# CY8CKIT-032_Schematic.net
KiCad netlist of a schematic drawn in EAGLE
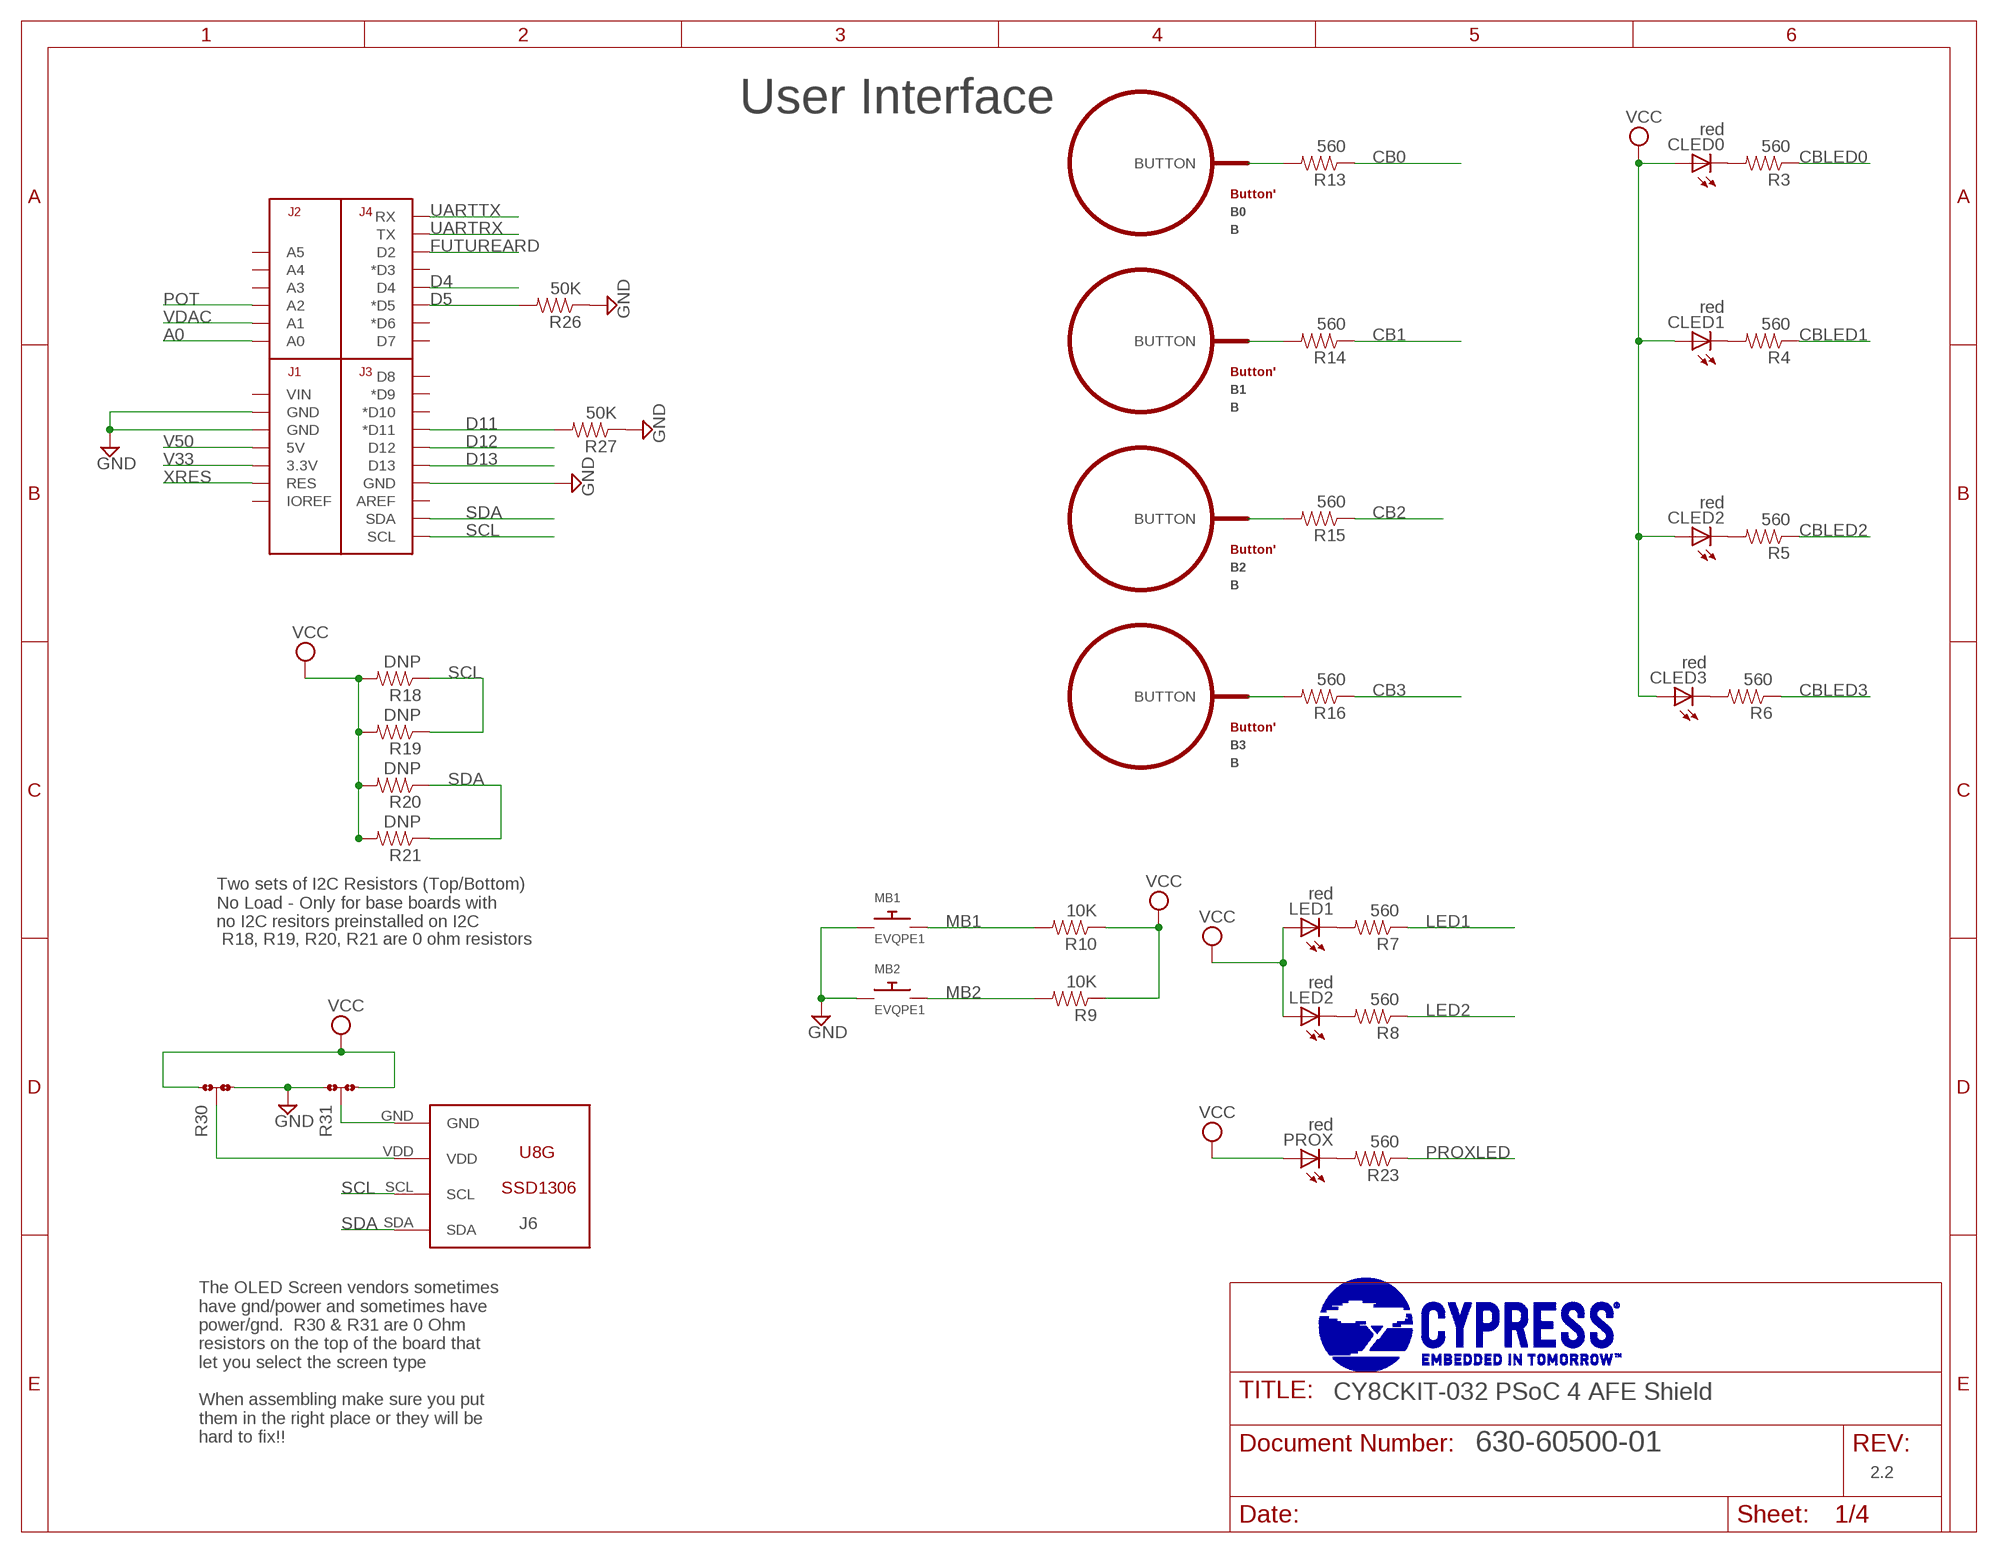
[diagram p0: schematic, sheet 1]
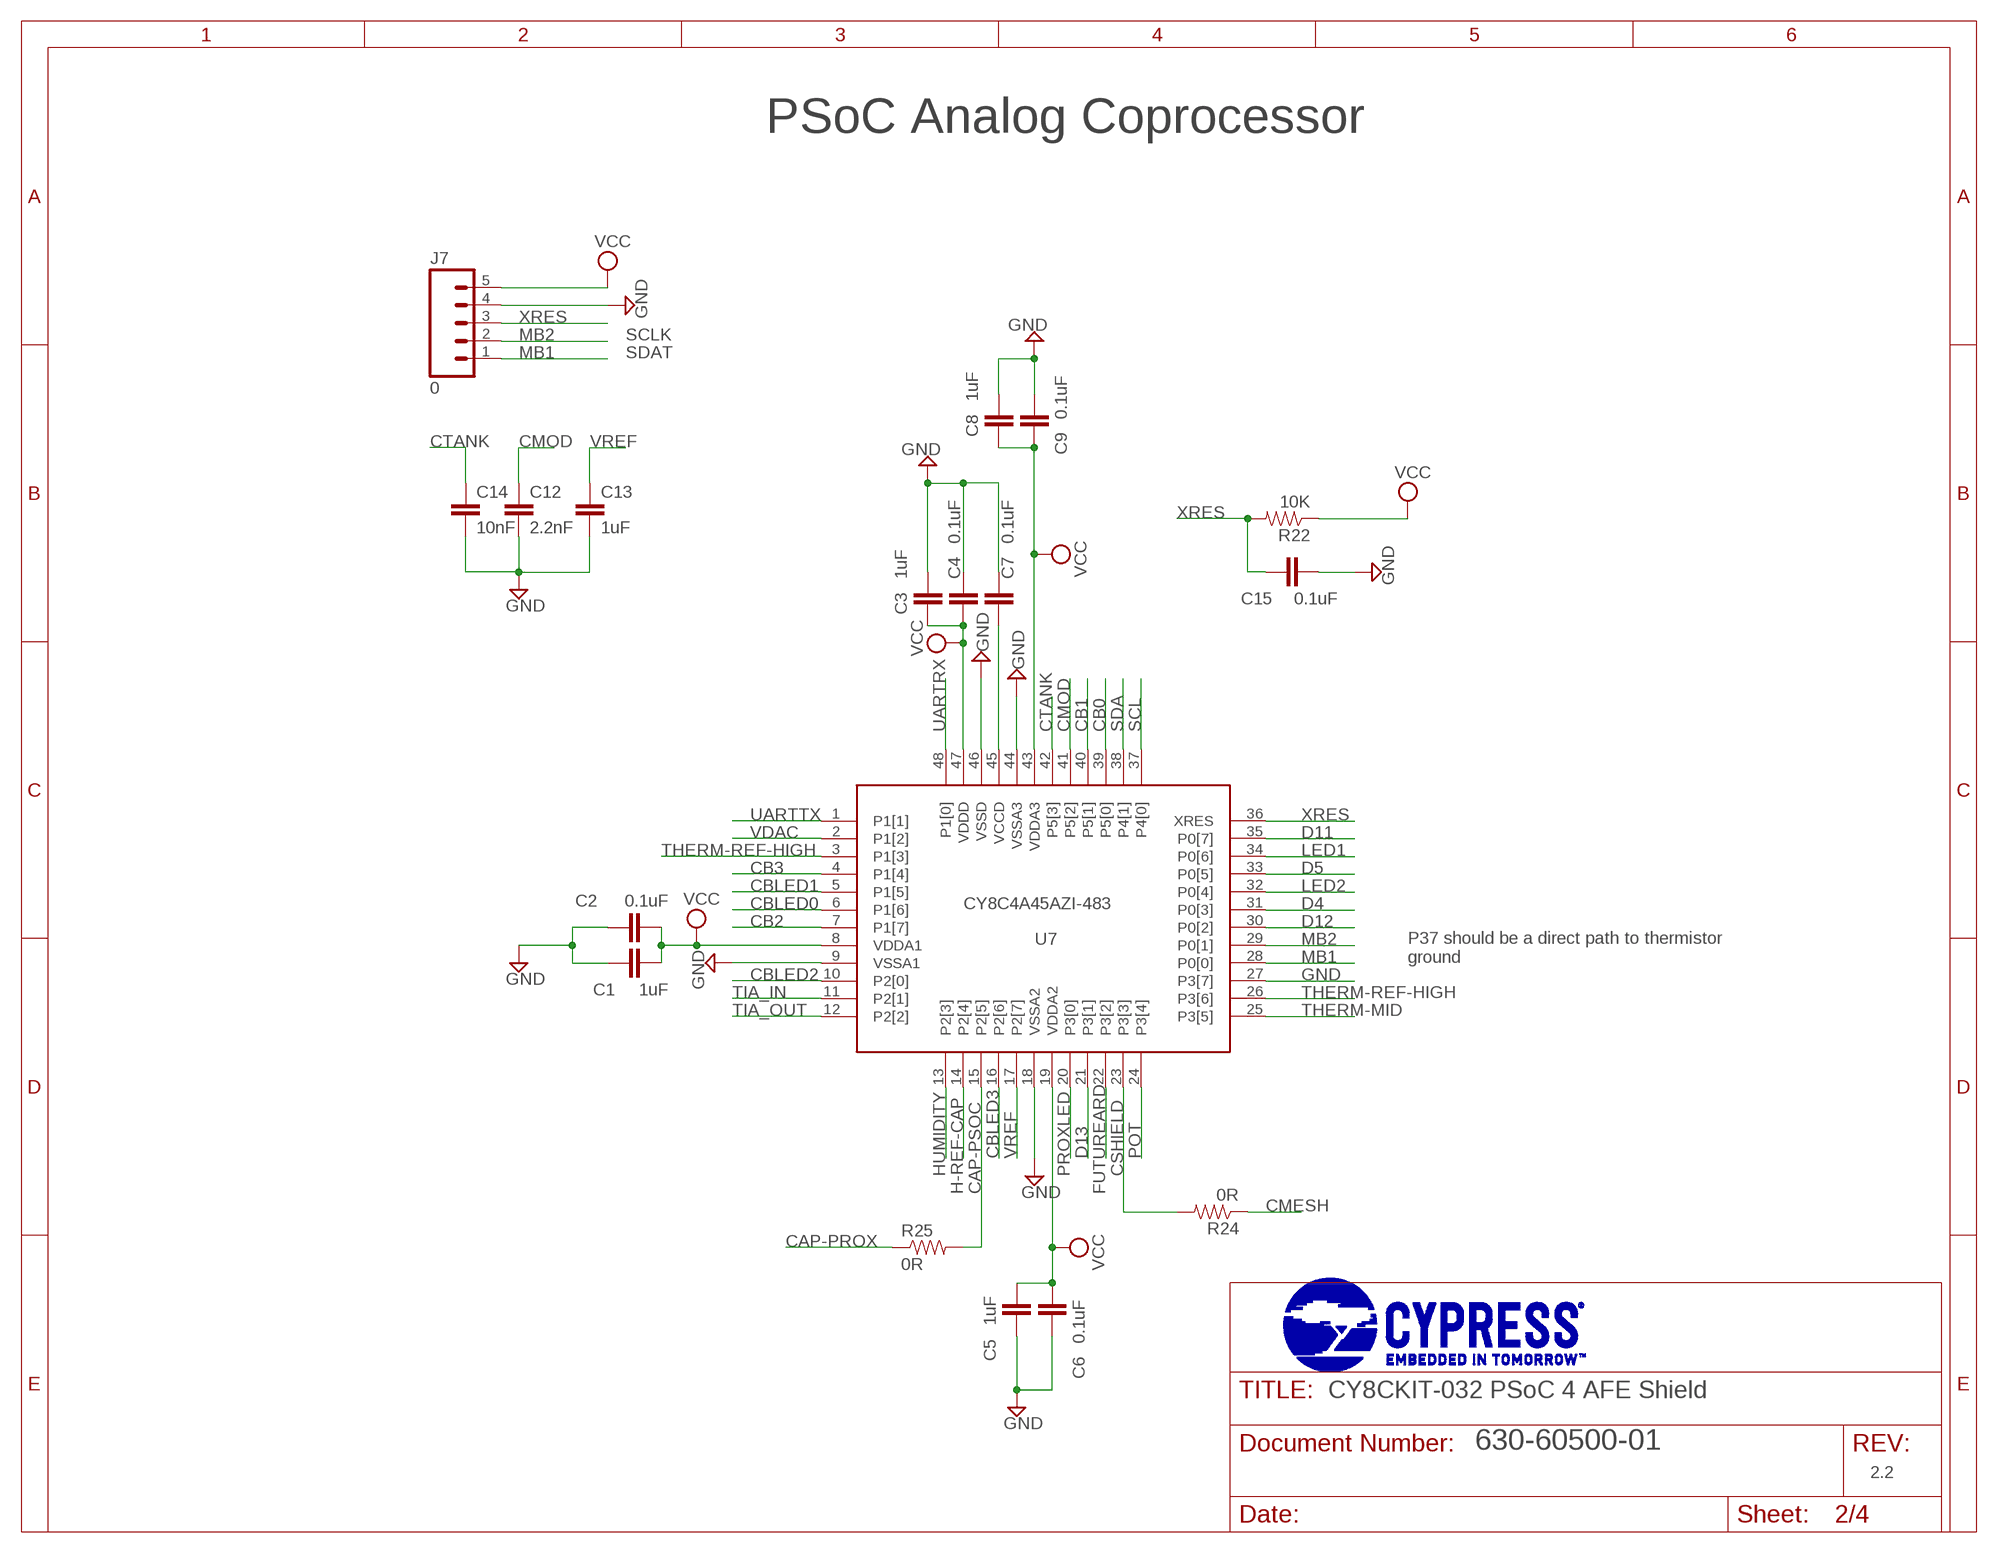
[diagram p1: schematic, sheet 2]
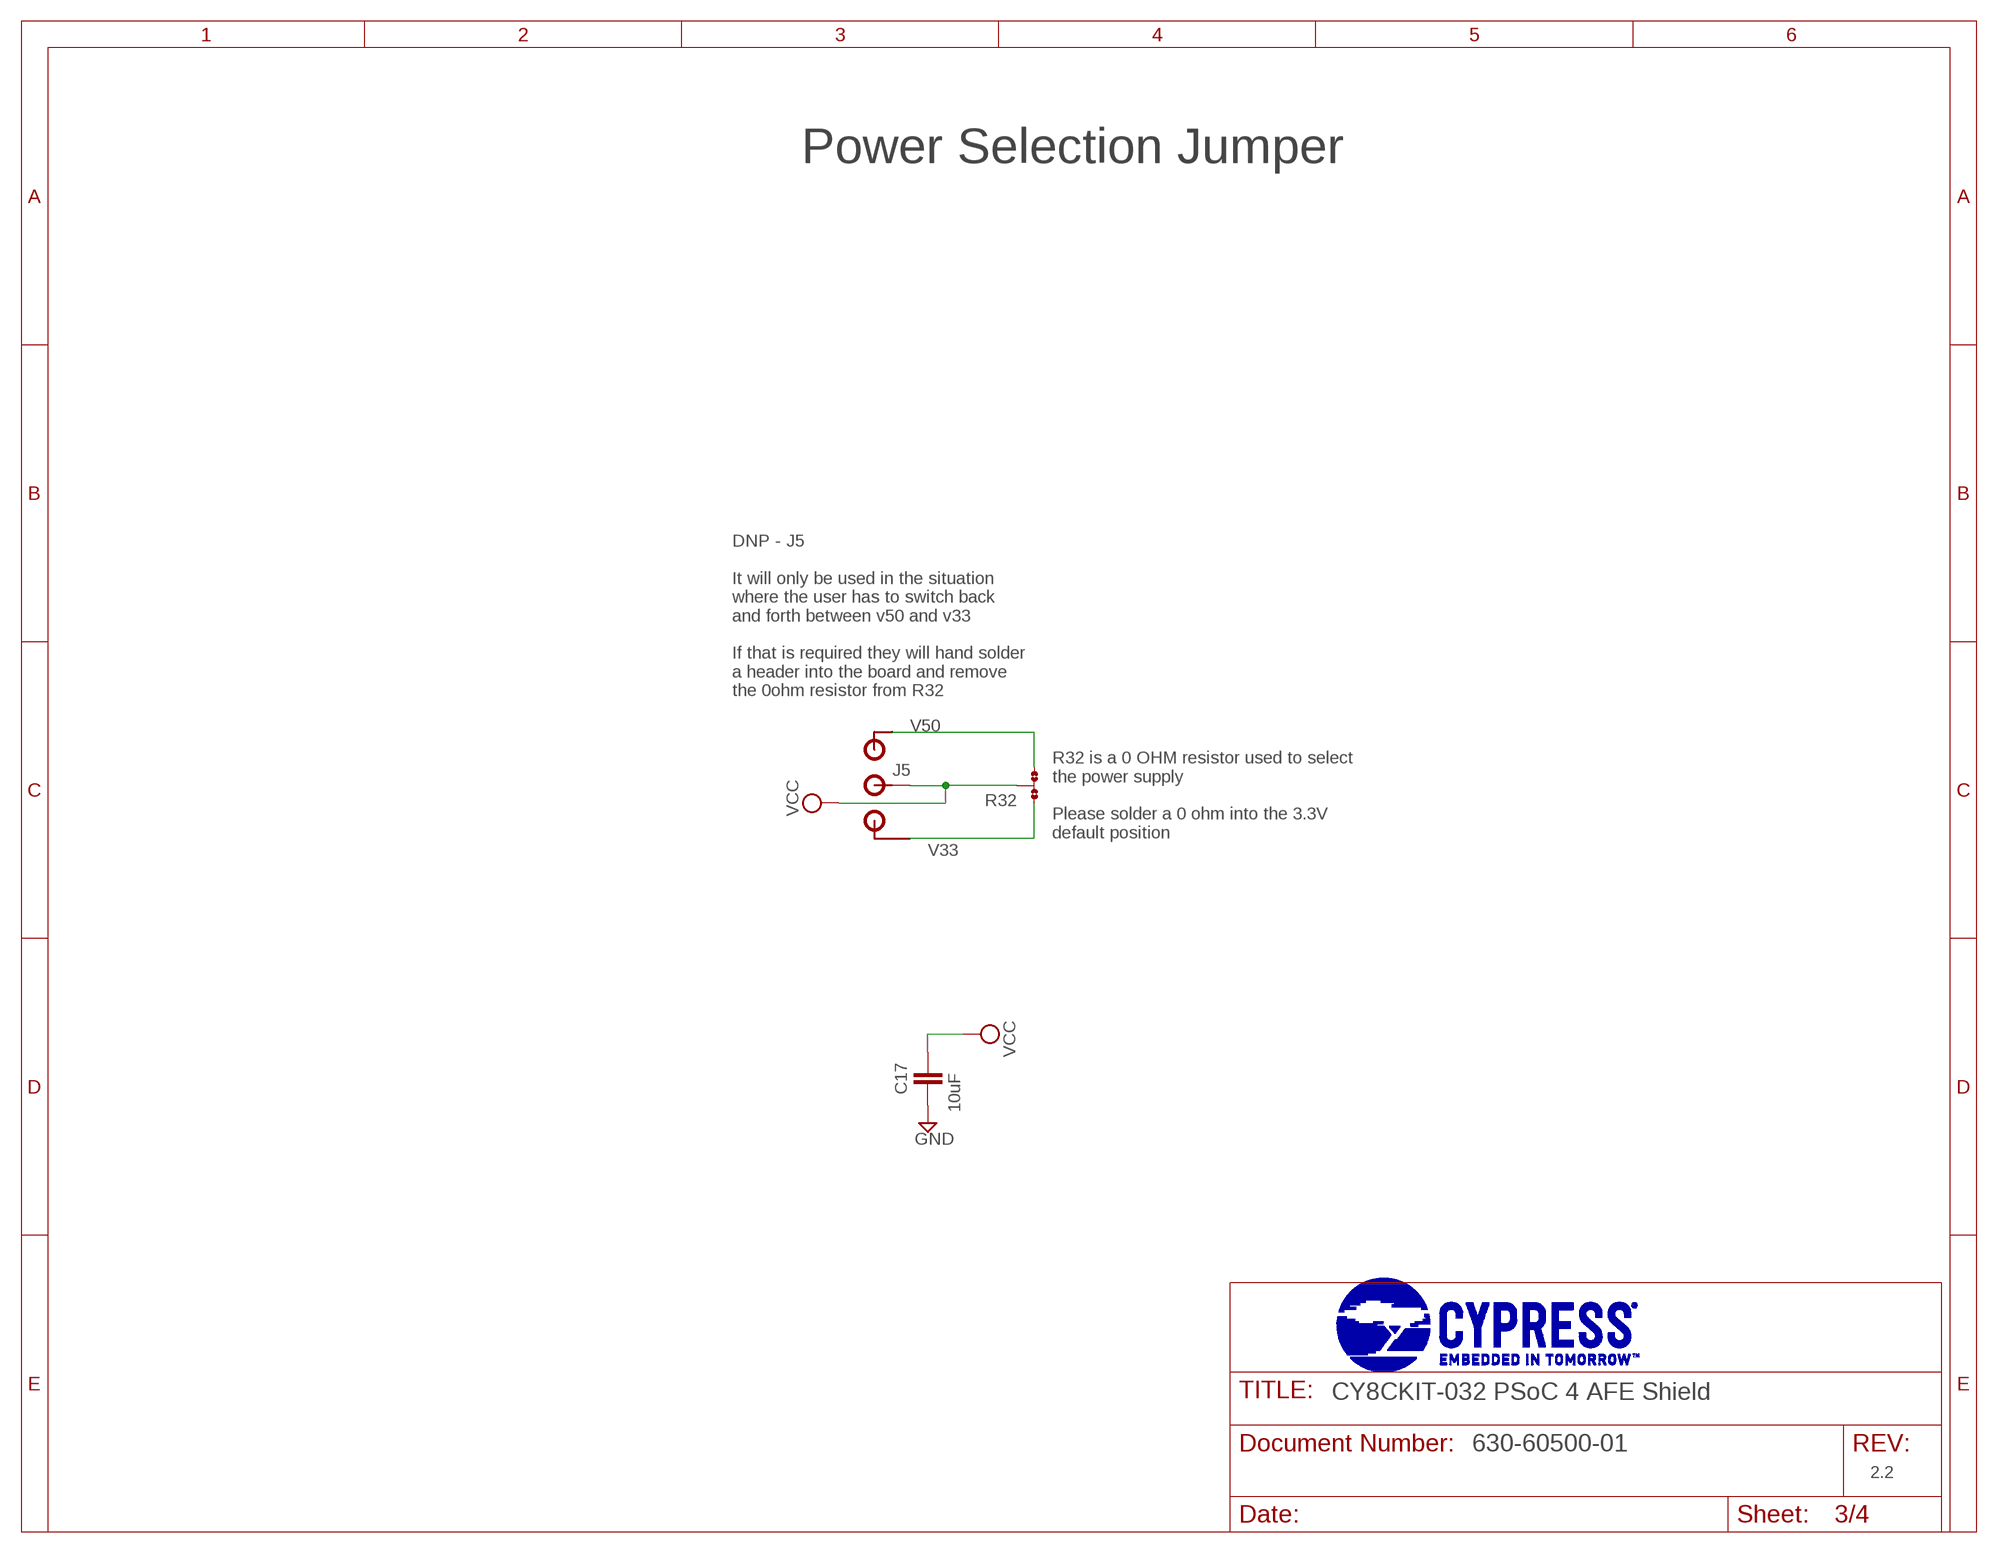
[diagram p2: schematic, sheet 3]
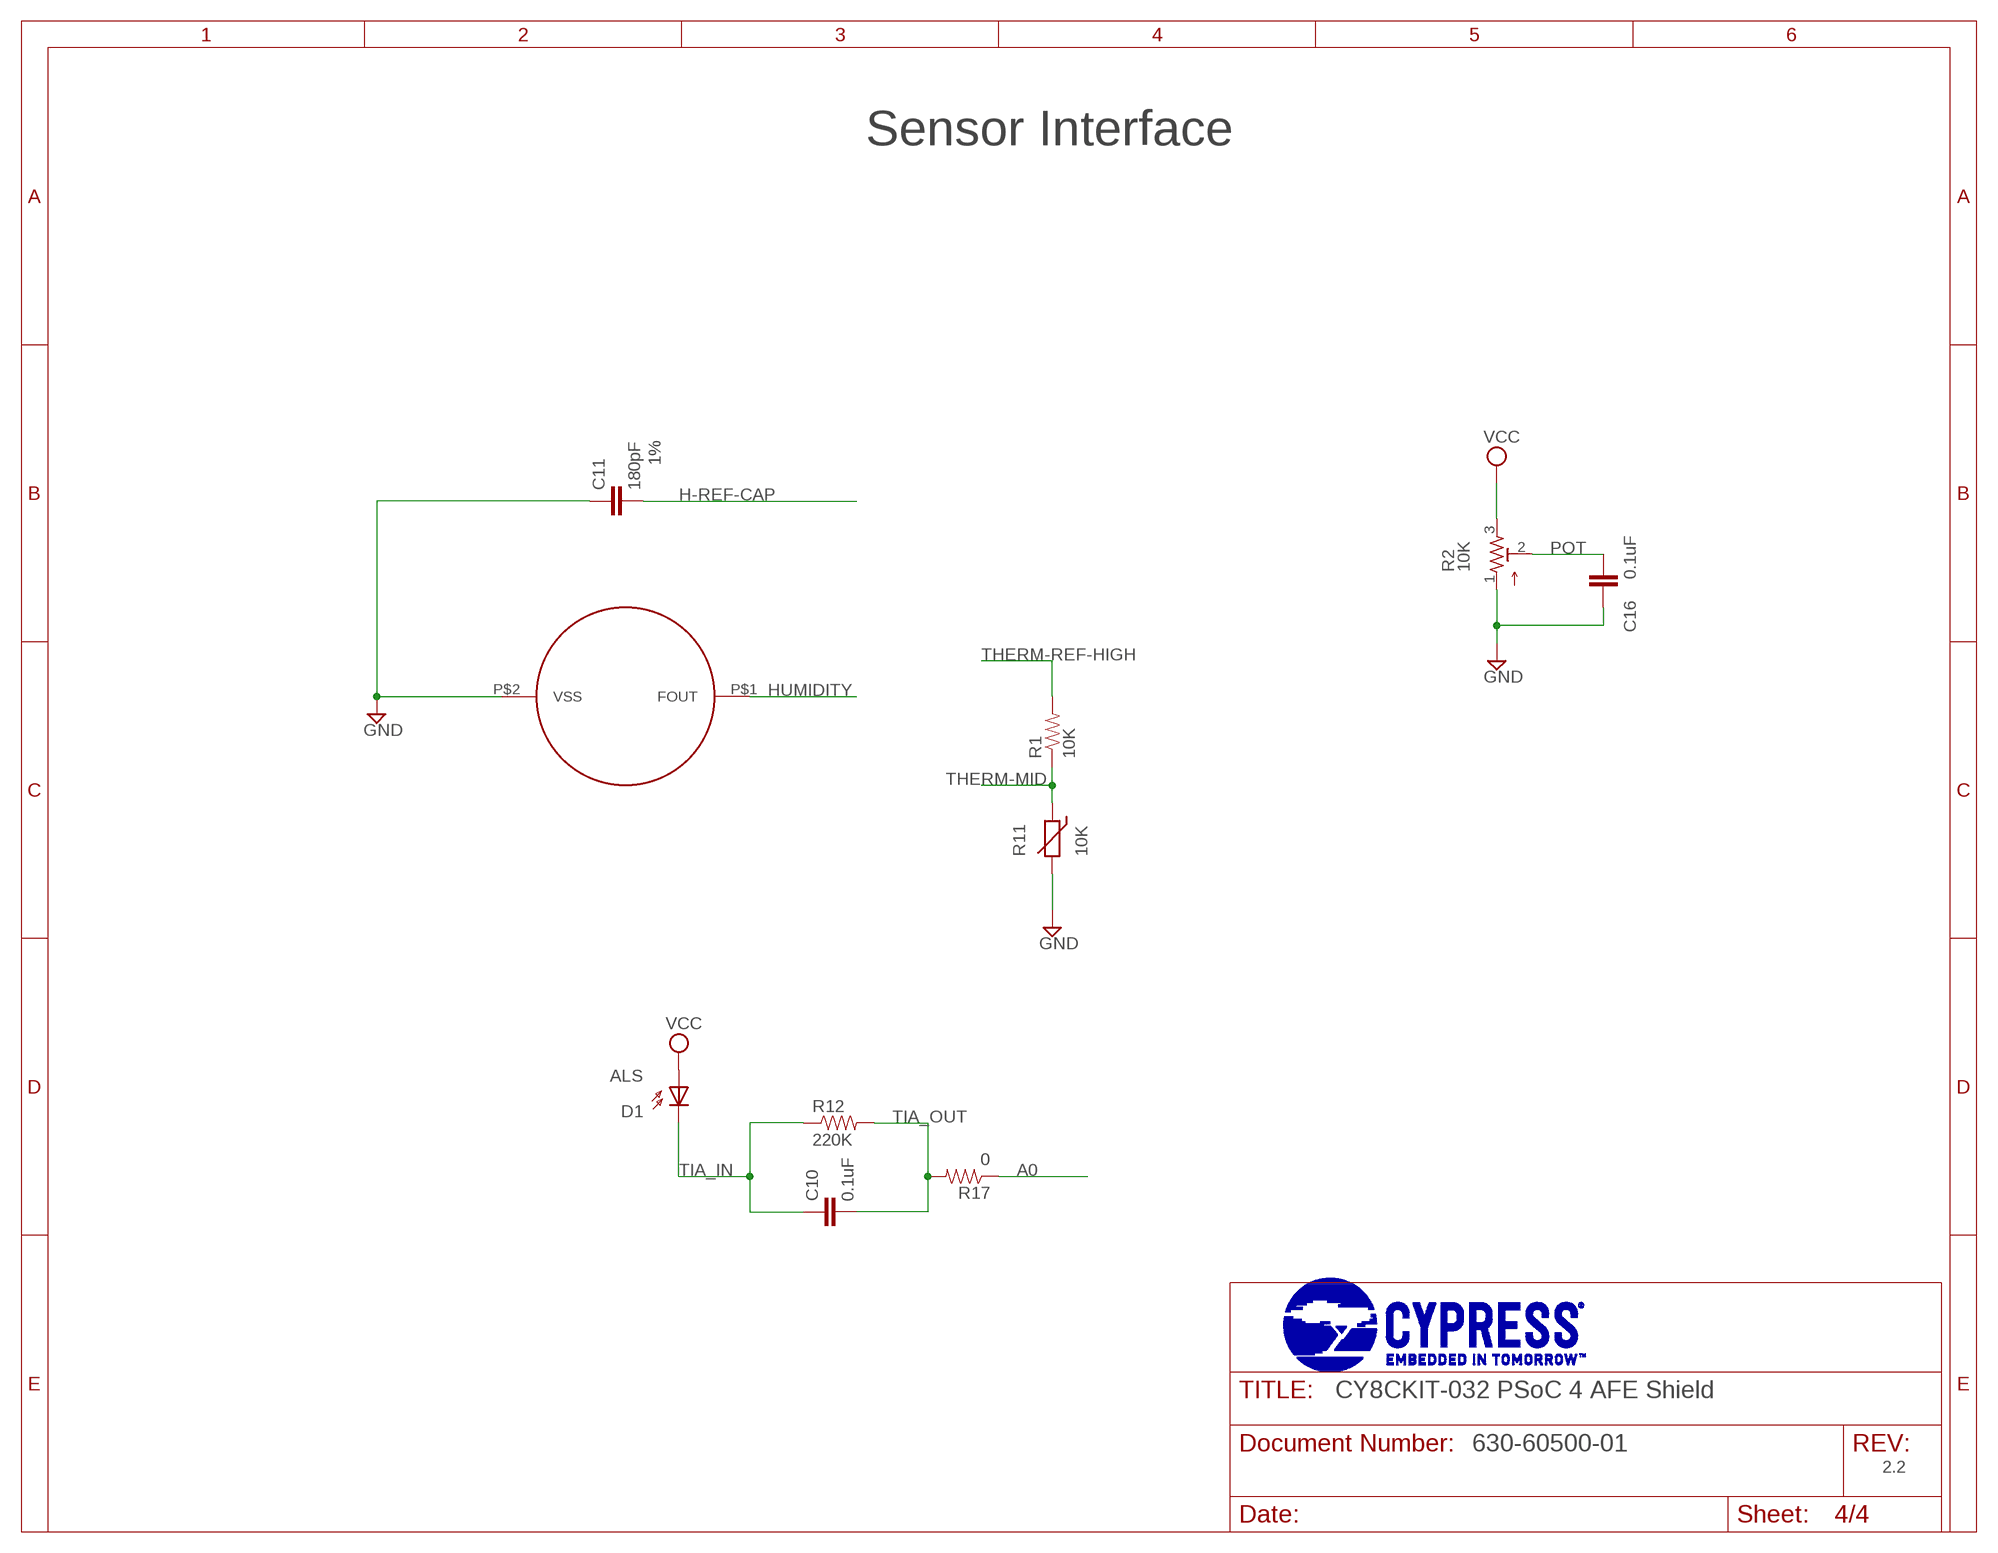
[diagram p3: schematic, sheet 4]

(export (version "E")
  (design (tool "Eeschema 10.0.6"))
  (components
    (comp (ref "C10")
      (value "0.1uF")
      (footprint "eagle-import:0603-CAP")
      (libsource (lib "eagle-import") (part "CAP0603-CAP"))
    )
    (comp (ref "C11")
      (value "180pF")
      (footprint "eagle-import:0603-CAP")
      (libsource (lib "eagle-import") (part "CAP0603-CAP"))
    )
    (comp (ref "C16")
      (value "0.1uF")
      (footprint "eagle-import:0603-CAP")
      (libsource (lib "eagle-import") (part "CAP0603-CAP"))
    )
    (comp (ref "D1")
      (value "ALS")
      (footprint "eagle-import:ALS")
      (libsource (lib "eagle-import") (part "ALS"))
    )
    (comp (ref "HUMIDITY")
      (value "HPP801A031")
      (footprint "eagle-import:HUMIDITY")
      (libsource (lib "eagle-import") (part "HPP801A031"))
    )
    (comp (ref "R1")
      (value "10K")
      (footprint "eagle-import:0603-RES")
      (libsource (lib "eagle-import") (part "RESISTOR0603"))
    )
    (comp (ref "R2")
      (value "10K")
      (footprint "eagle-import:3386P")
      (libsource (lib "eagle-import") (part "TRIM_US-3386P"))
    )
    (comp (ref "R11")
      (value "THERMISTOR-5")
      (footprint "eagle-import:R-5")
      (libsource (lib "eagle-import") (part "THERMISTOR-5"))
    )
    (comp (ref "R12")
      (value "220K")
      (footprint "eagle-import:0603-RES")
      (libsource (lib "eagle-import") (part "RESISTOR0603"))
    )
    (comp (ref "R17")
      (value "0")
      (footprint "eagle-import:0603-RES")
      (libsource (lib "eagle-import") (part "RESISTOR0603"))
    )
    (comp (ref "B0")
      (value "B")
      (footprint "eagle-import:BUTTON_PASSIVE_10MM")
      (libsource (lib "eagle-import") (part "BUTTON_PASSIVE10MM"))
    )
    (comp (ref "B1")
      (value "B")
      (footprint "eagle-import:BUTTON_PASSIVE_10MM")
      (libsource (lib "eagle-import") (part "BUTTON_PASSIVE10MM"))
    )
    (comp (ref "B2")
      (value "B")
      (footprint "eagle-import:BUTTON_PASSIVE_10MM")
      (libsource (lib "eagle-import") (part "BUTTON_PASSIVE10MM"))
    )
    (comp (ref "B3")
      (value "B")
      (footprint "eagle-import:BUTTON_PASSIVE_10MM")
      (libsource (lib "eagle-import") (part "BUTTON_PASSIVE10MM"))
    )
    (comp (ref "CLED0")
      (value "red")
      (footprint "eagle-import:CHIP-LED0603")
      (libsource (lib "eagle-import") (part "LEDCHIP-LED0603"))
    )
    (comp (ref "CLED1")
      (value "red")
      (footprint "eagle-import:CHIP-LED0603")
      (libsource (lib "eagle-import") (part "LEDCHIP-LED0603"))
    )
    (comp (ref "CLED2")
      (value "red")
      (footprint "eagle-import:CHIP-LED0603")
      (libsource (lib "eagle-import") (part "LEDCHIP-LED0603"))
    )
    (comp (ref "CLED3")
      (value "red")
      (footprint "eagle-import:CHIP-LED0603")
      (libsource (lib "eagle-import") (part "LEDCHIP-LED0603"))
    )
    (comp (ref "J6")
      (value "U8G-096-OLED")
      (footprint "eagle-import:096-SSD1306")
      (libsource (lib "eagle-import") (part "U8G-096-OLED"))
    )
    (comp (ref "LED1")
      (value "red")
      (footprint "eagle-import:CHIP-LED0603")
      (libsource (lib "eagle-import") (part "LEDCHIP-LED0603"))
    )
    (comp (ref "LED2")
      (value "red")
      (footprint "eagle-import:CHIP-LED0603")
      (libsource (lib "eagle-import") (part "LEDCHIP-LED0603"))
    )
    (comp (ref "MB1")
      (value "EVQPE1")
      (footprint "eagle-import:SWITCH")
      (libsource (lib "eagle-import") (part "EVQPE1"))
    )
    (comp (ref "MB2")
      (value "EVQPE1")
      (footprint "eagle-import:SWITCH")
      (libsource (lib "eagle-import") (part "EVQPE1"))
    )
    (comp (ref "PROX")
      (value "red")
      (footprint "eagle-import:CHIP-LED0603")
      (libsource (lib "eagle-import") (part "LEDCHIP-LED0603"))
    )
    (comp (ref "R3")
      (value "560")
      (footprint "eagle-import:0603-RES")
      (libsource (lib "eagle-import") (part "RESISTOR0603"))
    )
    (comp (ref "R4")
      (value "560")
      (footprint "eagle-import:0603-RES")
      (libsource (lib "eagle-import") (part "RESISTOR0603"))
    )
    (comp (ref "R5")
      (value "560")
      (footprint "eagle-import:0603-RES")
      (libsource (lib "eagle-import") (part "RESISTOR0603"))
    )
    (comp (ref "R6")
      (value "560")
      (footprint "eagle-import:0603-RES")
      (libsource (lib "eagle-import") (part "RESISTOR0603"))
    )
    (comp (ref "R7")
      (value "560")
      (footprint "eagle-import:0603-RES")
      (libsource (lib "eagle-import") (part "RESISTOR0603"))
    )
    (comp (ref "R8")
      (value "560")
      (footprint "eagle-import:0603-RES")
      (libsource (lib "eagle-import") (part "RESISTOR0603"))
    )
    (comp (ref "R9")
      (value "10K")
      (footprint "eagle-import:0603-RES")
      (libsource (lib "eagle-import") (part "RESISTOR0603"))
    )
    (comp (ref "R10")
      (value "10K")
      (footprint "eagle-import:0603-RES")
      (libsource (lib "eagle-import") (part "RESISTOR0603"))
    )
    (comp (ref "R13")
      (value "560")
      (footprint "eagle-import:0603-RES")
      (libsource (lib "eagle-import") (part "RESISTOR0603"))
    )
    (comp (ref "R14")
      (value "560")
      (footprint "eagle-import:0603-RES")
      (libsource (lib "eagle-import") (part "RESISTOR0603"))
    )
    (comp (ref "R15")
      (value "560")
      (footprint "eagle-import:0603-RES")
      (libsource (lib "eagle-import") (part "RESISTOR0603"))
    )
    (comp (ref "R16")
      (value "560")
      (footprint "eagle-import:0603-RES")
      (libsource (lib "eagle-import") (part "RESISTOR0603"))
    )
    (comp (ref "R18")
      (value "DNP")
      (footprint "eagle-import:0603-RES")
      (libsource (lib "eagle-import") (part "RESISTOR0603"))
    )
    (comp (ref "R19")
      (value "DNP")
      (footprint "eagle-import:0603-RES")
      (libsource (lib "eagle-import") (part "RESISTOR0603"))
    )
    (comp (ref "R20")
      (value "DNP")
      (footprint "eagle-import:0603-RES")
      (libsource (lib "eagle-import") (part "RESISTOR0603"))
    )
    (comp (ref "R21")
      (value "DNP")
      (footprint "eagle-import:0603-RES")
      (libsource (lib "eagle-import") (part "RESISTOR0603"))
    )
    (comp (ref "R23")
      (value "560")
      (footprint "eagle-import:0603-RES")
      (libsource (lib "eagle-import") (part "RESISTOR0603"))
    )
    (comp (ref "R26")
      (value "50K")
      (footprint "eagle-import:0603-RES")
      (libsource (lib "eagle-import") (part "RESISTOR0603"))
    )
    (comp (ref "R27")
      (value "50K")
      (footprint "eagle-import:0603-RES")
      (libsource (lib "eagle-import") (part "RESISTOR0603"))
    )
    (comp (ref "R30")
      (value "JMP-3-1_2")
      (footprint "eagle-import:JMP-3-1_2")
      (libsource (lib "eagle-import") (part "JMP-3-1_2"))
    )
    (comp (ref "R31")
      (value "JMP-3-2_3")
      (footprint "eagle-import:JMP-3-2_3")
      (libsource (lib "eagle-import") (part "JMP-3-2_3"))
    )
    (comp (ref "U$1")
      (value "ARDUINO_R3_SHIELDNOLABELS")
      (footprint "eagle-import:UNO_R3_SHIELD_NOLABELS")
      (libsource (lib "eagle-import") (part "ARDUINO_R3_SHIELDNOLABELS"))
    )
    (comp (ref "C1")
      (value "1uF")
      (footprint "eagle-import:0603-CAP")
      (libsource (lib "eagle-import") (part "CAP0603-CAP"))
    )
    (comp (ref "C2")
      (value "0.1uF")
      (footprint "eagle-import:0603-CAP")
      (libsource (lib "eagle-import") (part "CAP0603-CAP"))
    )
    (comp (ref "C3")
      (value "1uF")
      (footprint "eagle-import:0603-CAP")
      (libsource (lib "eagle-import") (part "CAP0603-CAP"))
    )
    (comp (ref "C4")
      (value "0.1uF")
      (footprint "eagle-import:0603-CAP")
      (libsource (lib "eagle-import") (part "CAP0603-CAP"))
    )
    (comp (ref "C5")
      (value "1uF")
      (footprint "eagle-import:0603-CAP")
      (libsource (lib "eagle-import") (part "CAP0603-CAP"))
    )
    (comp (ref "C6")
      (value "0.1uF")
      (footprint "eagle-import:0603-CAP")
      (libsource (lib "eagle-import") (part "CAP0603-CAP"))
    )
    (comp (ref "C7")
      (value "0.1uF")
      (footprint "eagle-import:0603-CAP")
      (libsource (lib "eagle-import") (part "CAP0603-CAP"))
    )
    (comp (ref "C8")
      (value "1uF")
      (footprint "eagle-import:0603-CAP")
      (libsource (lib "eagle-import") (part "CAP0603-CAP"))
    )
    (comp (ref "C9")
      (value "0.1uF")
      (footprint "eagle-import:0603-CAP")
      (libsource (lib "eagle-import") (part "CAP0603-CAP"))
    )
    (comp (ref "C12")
      (value "2.2nF")
      (footprint "eagle-import:0603-CAP")
      (libsource (lib "eagle-import") (part "CAP0603-CAP"))
    )
    (comp (ref "C13")
      (value "1uF")
      (footprint "eagle-import:0603-CAP")
      (libsource (lib "eagle-import") (part "CAP0603-CAP"))
    )
    (comp (ref "C14")
      (value "10nF")
      (footprint "eagle-import:0603-CAP")
      (libsource (lib "eagle-import") (part "CAP0603-CAP"))
    )
    (comp (ref "C15")
      (value "0.1uF")
      (footprint "eagle-import:0603-CAP")
      (libsource (lib "eagle-import") (part "CAP0603-CAP"))
    )
    (comp (ref "J7")
      (value "0")
      (footprint "eagle-import:1X05_LOCK")
      (libsource (lib "eagle-import") (part "M05LOCK"))
    )
    (comp (ref "R22")
      (value "10K")
      (footprint "eagle-import:0603-RES")
      (libsource (lib "eagle-import") (part "RESISTOR0603"))
    )
    (comp (ref "R24")
      (value "0R")
      (footprint "eagle-import:0603-RES")
      (libsource (lib "eagle-import") (part "RESISTOR0603"))
    )
    (comp (ref "R25")
      (value "0R")
      (footprint "eagle-import:0603-RES")
      (libsource (lib "eagle-import") (part "RESISTOR0603"))
    )
    (comp (ref "U7")
      (value "CY8C4A45-48")
      (footprint "eagle-import:TQFP-7X7-48")
      (libsource (lib "eagle-import") (part "CY8C4A45-48"))
    )
    (comp (ref "C17")
      (value "10uF")
      (footprint "eagle-import:0603-CAP")
      (libsource (lib "eagle-import") (part "CAP0603-CAP"))
    )
    (comp (ref "J5")
      (value "vcc")
      (footprint "eagle-import:JMP-3-NO-PTH-2.54")
      (libsource (lib "eagle-import") (part "JMP-3-PTH-PTH"))
    )
    (comp (ref "R32")
      (value "3.3v")
      (footprint "eagle-import:JMP-3-NO")
      (libsource (lib "eagle-import") (part "JMP-3-NO"))
    )
  )
  (nets
    (net (code "1") (name "A0") (class "Default")
      (node (ref "R17") (pin "1") (pinfunction "1_1") (pintype "passive"))
      (node (ref "U$1") (pin "A0") (pinfunction "A0_A0") (pintype "bidirectional"))
    )
    (net (code "2") (name "CAP-PROX") (class "Default")
      (node (ref "R25") (pin "1") (pinfunction "1_1") (pintype "passive"))
    )
    (net (code "3") (name "CAP-PSOC") (class "Default")
      (node (ref "R25") (pin "2") (pinfunction "2_2") (pintype "passive"))
      (node (ref "U7") (pin "15") (pinfunction "P2[5]_15") (pintype "bidirectional"))
    )
    (net (code "4") (name "CB0") (class "Default")
      (node (ref "R13") (pin "1") (pinfunction "1_1") (pintype "passive"))
      (node (ref "U7") (pin "39") (pinfunction "P5[0]_39") (pintype "bidirectional"))
    )
    (net (code "5") (name "CB1") (class "Default")
      (node (ref "R14") (pin "1") (pinfunction "1_1") (pintype "passive"))
      (node (ref "U7") (pin "40") (pinfunction "P5[1]_40") (pintype "bidirectional"))
    )
    (net (code "6") (name "CB2") (class "Default")
      (node (ref "R15") (pin "1") (pinfunction "1_1") (pintype "passive"))
      (node (ref "U7") (pin "7") (pinfunction "P1[7]_7") (pintype "bidirectional"))
    )
    (net (code "7") (name "CB3") (class "Default")
      (node (ref "R16") (pin "1") (pinfunction "1_1") (pintype "passive"))
      (node (ref "U7") (pin "4") (pinfunction "P1[4]_4") (pintype "bidirectional"))
    )
    (net (code "8") (name "CBLED0") (class "Default")
      (node (ref "R3") (pin "1") (pinfunction "1_1") (pintype "passive"))
      (node (ref "U7") (pin "6") (pinfunction "P1[6]_6") (pintype "bidirectional"))
    )
    (net (code "9") (name "CBLED1") (class "Default")
      (node (ref "R4") (pin "1") (pinfunction "1_1") (pintype "passive"))
      (node (ref "U7") (pin "5") (pinfunction "P1[5]_5") (pintype "bidirectional"))
    )
    (net (code "10") (name "CBLED2") (class "Default")
      (node (ref "R5") (pin "1") (pinfunction "1_1") (pintype "passive"))
      (node (ref "U7") (pin "10") (pinfunction "P2[0]_10") (pintype "bidirectional"))
    )
    (net (code "11") (name "CBLED3") (class "Default")
      (node (ref "R6") (pin "1") (pinfunction "1_1") (pintype "passive"))
      (node (ref "U7") (pin "16") (pinfunction "P2[6]_16") (pintype "bidirectional"))
    )
    (net (code "12") (name "CMESH") (class "Default")
      (node (ref "R24") (pin "1") (pinfunction "1_1") (pintype "passive"))
    )
    (net (code "13") (name "CMOD") (class "Default")
      (node (ref "C12") (pin "1") (pinfunction "1_1") (pintype "passive"))
      (node (ref "U7") (pin "41") (pinfunction "P5[2]_41") (pintype "bidirectional"))
    )
    (net (code "14") (name "CSHIELD") (class "Default")
      (node (ref "R24") (pin "2") (pinfunction "2_2") (pintype "passive"))
      (node (ref "U7") (pin "23") (pinfunction "P3[3]_23") (pintype "bidirectional"))
    )
    (net (code "15") (name "CTANK") (class "Default")
      (node (ref "C14") (pin "1") (pinfunction "1_1") (pintype "passive"))
      (node (ref "U7") (pin "42") (pinfunction "P5[3]_42") (pintype "bidirectional"))
    )
    (net (code "16") (name "D4") (class "Default")
      (node (ref "U$1") (pin "D4") (pinfunction "D4_D4") (pintype "bidirectional"))
      (node (ref "U7") (pin "31") (pinfunction "P0[3]_31") (pintype "bidirectional"))
    )
    (net (code "17") (name "D5") (class "Default")
      (node (ref "R26") (pin "2") (pinfunction "2_2") (pintype "passive"))
      (node (ref "U$1") (pin "D5") (pinfunction "*D5_D5") (pintype "bidirectional"))
      (node (ref "U7") (pin "33") (pinfunction "P0[5]_33") (pintype "bidirectional"))
    )
    (net (code "18") (name "D11") (class "Default")
      (node (ref "R27") (pin "2") (pinfunction "2_2") (pintype "passive"))
      (node (ref "U$1") (pin "D11") (pinfunction "*D11_D11") (pintype "bidirectional"))
      (node (ref "U7") (pin "35") (pinfunction "P0[7]_35") (pintype "bidirectional"))
    )
    (net (code "19") (name "D12") (class "Default")
      (node (ref "U$1") (pin "D12") (pinfunction "D12_D12") (pintype "bidirectional"))
      (node (ref "U7") (pin "30") (pinfunction "P0[2]_30") (pintype "bidirectional"))
    )
    (net (code "20") (name "D13") (class "Default")
      (node (ref "U$1") (pin "D13") (pinfunction "D13_D13") (pintype "bidirectional"))
      (node (ref "U7") (pin "21") (pinfunction "P3[1]_21") (pintype "bidirectional"))
    )
    (net (code "21") (name "FUTUREARD") (class "Default")
      (node (ref "U$1") (pin "D2") (pinfunction "D2_D2") (pintype "bidirectional"))
      (node (ref "U7") (pin "22") (pinfunction "P3[2]_22") (pintype "bidirectional"))
    )
    (net (code "22") (name "GND") (class "Default")
      (node (ref "C1") (pin "1") (pinfunction "1_1") (pintype "passive"))
      (node (ref "C11") (pin "1") (pinfunction "1_1") (pintype "passive"))
      (node (ref "C12") (pin "2") (pinfunction "2_2") (pintype "passive"))
      (node (ref "C13") (pin "2") (pinfunction "2_2") (pintype "passive"))
      (node (ref "C14") (pin "2") (pinfunction "2_2") (pintype "passive"))
      (node (ref "C15") (pin "1") (pinfunction "1_1") (pintype "passive"))
      (node (ref "C16") (pin "2") (pinfunction "2_2") (pintype "passive"))
      (node (ref "C17") (pin "2") (pinfunction "2_2") (pintype "passive"))
      (node (ref "C2") (pin "1") (pinfunction "1_1") (pintype "passive"))
      (node (ref "C3") (pin "1") (pinfunction "1_1") (pintype "passive"))
      (node (ref "C4") (pin "1") (pinfunction "1_1") (pintype "passive"))
      (node (ref "C5") (pin "2") (pinfunction "2_2") (pintype "passive"))
      (node (ref "C6") (pin "2") (pinfunction "2_2") (pintype "passive"))
      (node (ref "C7") (pin "1") (pinfunction "1_1") (pintype "passive"))
      (node (ref "C8") (pin "1") (pinfunction "1_1") (pintype "passive"))
      (node (ref "C9") (pin "1") (pinfunction "1_1") (pintype "passive"))
      (node (ref "HUMIDITY") (pin "P$2") (pinfunction "VSS_P$2") (pintype "bidirectional"))
      (node (ref "J7") (pin "4") (pinfunction "4_4") (pintype "passive"))
      (node (ref "MB1") (pin "P$1") (pinfunction "P$1_P$1") (pintype "passive"))
      (node (ref "MB2") (pin "P$1") (pinfunction "P$1_P$1") (pintype "passive"))
      (node (ref "R11") (pin "2") (pinfunction "2_2") (pintype "passive"))
      (node (ref "R2") (pin "1") (pinfunction "1_1") (pintype "passive"))
      (node (ref "R26") (pin "1") (pinfunction "1_1") (pintype "passive"))
      (node (ref "R27") (pin "1") (pinfunction "1_1") (pintype "passive"))
      (node (ref "R30") (pin "3") (pinfunction "3_3") (pintype "passive"))
      (node (ref "R31") (pin "1") (pinfunction "1_1") (pintype "passive"))
      (node (ref "U$1") (pin "GND@0") (pinfunction "GND_GND@0") (pintype "bidirectional"))
      (node (ref "U$1") (pin "GND@1") (pinfunction "GND_GND@1") (pintype "bidirectional"))
      (node (ref "U$1") (pin "GND@2") (pinfunction "GND_GND@2") (pintype "bidirectional"))
      (node (ref "U7") (pin "18") (pinfunction "VSSA2_18") (pintype "bidirectional"))
      (node (ref "U7") (pin "27") (pinfunction "P3[7]_27") (pintype "bidirectional"))
      (node (ref "U7") (pin "44") (pinfunction "VSSA3_44") (pintype "bidirectional"))
      (node (ref "U7") (pin "46") (pinfunction "VSSD_46") (pintype "bidirectional"))
      (node (ref "U7") (pin "9") (pinfunction "VSSA1_9") (pintype "bidirectional"))
    )
    (net (code "23") (name "H-REF-CAP") (class "Default")
      (node (ref "C11") (pin "2") (pinfunction "2_2") (pintype "passive"))
      (node (ref "U7") (pin "14") (pinfunction "P2[4]_14") (pintype "bidirectional"))
    )
    (net (code "24") (name "HUMIDITY") (class "Default")
      (node (ref "HUMIDITY") (pin "P$1") (pinfunction "FOUT_P$1") (pintype "bidirectional"))
      (node (ref "U7") (pin "13") (pinfunction "P2[3]_13") (pintype "bidirectional"))
    )
    (net (code "25") (name "LED1") (class "Default")
      (node (ref "R7") (pin "1") (pinfunction "1_1") (pintype "passive"))
      (node (ref "U7") (pin "34") (pinfunction "P0[6]_34") (pintype "bidirectional"))
    )
    (net (code "26") (name "LED2") (class "Default")
      (node (ref "R8") (pin "1") (pinfunction "1_1") (pintype "passive"))
      (node (ref "U7") (pin "32") (pinfunction "P0[4]_32") (pintype "bidirectional"))
    )
    (net (code "27") (name "MB1") (class "Default")
      (node (ref "J7") (pin "1") (pinfunction "1_1") (pintype "passive"))
      (node (ref "MB1") (pin "P$2") (pinfunction "P$2_P$2") (pintype "passive"))
      (node (ref "R10") (pin "2") (pinfunction "2_2") (pintype "passive"))
      (node (ref "U7") (pin "28") (pinfunction "P0[0]_28") (pintype "bidirectional"))
    )
    (net (code "28") (name "MB2") (class "Default")
      (node (ref "J7") (pin "2") (pinfunction "2_2") (pintype "passive"))
      (node (ref "MB2") (pin "P$2") (pinfunction "P$2_P$2") (pintype "passive"))
      (node (ref "R9") (pin "2") (pinfunction "2_2") (pintype "passive"))
      (node (ref "U7") (pin "29") (pinfunction "P0[1]_29") (pintype "bidirectional"))
    )
    (net (code "29") (name "Net-(B0-PadBUTTON)") (class "Default")
      (node (ref "B0") (pin "BUTTON") (pinfunction "BUTTON_BUTTON") (pintype "passive"))
      (node (ref "R13") (pin "2") (pinfunction "2_2") (pintype "passive"))
    )
    (net (code "30") (name "Net-(B1-PadBUTTON)") (class "Default")
      (node (ref "B1") (pin "BUTTON") (pinfunction "BUTTON_BUTTON") (pintype "passive"))
      (node (ref "R14") (pin "2") (pinfunction "2_2") (pintype "passive"))
    )
    (net (code "31") (name "Net-(B2-PadBUTTON)") (class "Default")
      (node (ref "B2") (pin "BUTTON") (pinfunction "BUTTON_BUTTON") (pintype "passive"))
      (node (ref "R15") (pin "2") (pinfunction "2_2") (pintype "passive"))
    )
    (net (code "32") (name "Net-(B3-PadBUTTON)") (class "Default")
      (node (ref "B3") (pin "BUTTON") (pinfunction "BUTTON_BUTTON") (pintype "passive"))
      (node (ref "R16") (pin "2") (pinfunction "2_2") (pintype "passive"))
    )
    (net (code "33") (name "Net-(CLED0-PadC)") (class "Default")
      (node (ref "CLED0") (pin "C") (pinfunction "C_C") (pintype "passive"))
      (node (ref "R3") (pin "2") (pinfunction "2_2") (pintype "passive"))
    )
    (net (code "34") (name "Net-(CLED1-PadC)") (class "Default")
      (node (ref "CLED1") (pin "C") (pinfunction "C_C") (pintype "passive"))
      (node (ref "R4") (pin "2") (pinfunction "2_2") (pintype "passive"))
    )
    (net (code "35") (name "Net-(CLED2-PadC)") (class "Default")
      (node (ref "CLED2") (pin "C") (pinfunction "C_C") (pintype "passive"))
      (node (ref "R5") (pin "2") (pinfunction "2_2") (pintype "passive"))
    )
    (net (code "36") (name "Net-(CLED3-PadC)") (class "Default")
      (node (ref "CLED3") (pin "C") (pinfunction "C_C") (pintype "passive"))
      (node (ref "R6") (pin "2") (pinfunction "2_2") (pintype "passive"))
    )
    (net (code "37") (name "Net-(J6-PadGND)") (class "Default")
      (node (ref "J6") (pin "GND") (pinfunction "GND_GND") (pintype "power_in"))
      (node (ref "R31") (pin "2") (pinfunction "2_2") (pintype "passive"))
    )
    (net (code "38") (name "Net-(J6-PadVDD)") (class "Default")
      (node (ref "J6") (pin "VDD") (pinfunction "VDD_VDD") (pintype "power_in"))
      (node (ref "R30") (pin "2") (pinfunction "2_2") (pintype "passive"))
    )
    (net (code "39") (name "Net-(LED1-PadC)") (class "Default")
      (node (ref "LED1") (pin "C") (pinfunction "C_C") (pintype "passive"))
      (node (ref "R7") (pin "2") (pinfunction "2_2") (pintype "passive"))
    )
    (net (code "40") (name "Net-(LED2-PadC)") (class "Default")
      (node (ref "LED2") (pin "C") (pinfunction "C_C") (pintype "passive"))
      (node (ref "R8") (pin "2") (pinfunction "2_2") (pintype "passive"))
    )
    (net (code "41") (name "Net-(PROX-PadC)") (class "Default")
      (node (ref "PROX") (pin "C") (pinfunction "C_C") (pintype "passive"))
      (node (ref "R23") (pin "2") (pinfunction "2_2") (pintype "passive"))
    )
    (net (code "42") (name "Net-(U7-VCCD)") (class "Default")
      (node (ref "C7") (pin "2") (pinfunction "2_2") (pintype "passive"))
      (node (ref "U7") (pin "45") (pinfunction "VCCD_45") (pintype "bidirectional"))
    )
    (net (code "43") (name "POT") (class "Default")
      (node (ref "C16") (pin "1") (pinfunction "1_1") (pintype "passive"))
      (node (ref "R2") (pin "2") (pinfunction "2_2") (pintype "passive"))
      (node (ref "U$1") (pin "A2") (pinfunction "A2_A2") (pintype "bidirectional"))
      (node (ref "U7") (pin "24") (pinfunction "P3[4]_24") (pintype "bidirectional"))
    )
    (net (code "44") (name "PROXLED") (class "Default")
      (node (ref "R23") (pin "1") (pinfunction "1_1") (pintype "passive"))
      (node (ref "U7") (pin "20") (pinfunction "P3[0]_20") (pintype "bidirectional"))
    )
    (net (code "45") (name "SCL") (class "Default")
      (node (ref "J6") (pin "SCL") (pinfunction "SCL_SCL") (pintype "bidirectional"))
      (node (ref "R18") (pin "1") (pinfunction "1_1") (pintype "passive"))
      (node (ref "R19") (pin "1") (pinfunction "1_1") (pintype "passive"))
      (node (ref "U$1") (pin "SCL") (pinfunction "SCL_SCL") (pintype "bidirectional"))
      (node (ref "U7") (pin "37") (pinfunction "P4[0]_37") (pintype "bidirectional"))
    )
    (net (code "46") (name "SDA") (class "Default")
      (node (ref "J6") (pin "SDA") (pinfunction "SDA_SDA") (pintype "bidirectional"))
      (node (ref "R20") (pin "1") (pinfunction "1_1") (pintype "passive"))
      (node (ref "R21") (pin "1") (pinfunction "1_1") (pintype "passive"))
      (node (ref "U$1") (pin "SDA") (pinfunction "SDA_SDA") (pintype "bidirectional"))
      (node (ref "U7") (pin "38") (pinfunction "P4[1]_38") (pintype "bidirectional"))
    )
    (net (code "47") (name "THERM-MID") (class "Default")
      (node (ref "R1") (pin "1") (pinfunction "1_1") (pintype "passive"))
      (node (ref "R11") (pin "1") (pinfunction "1_1") (pintype "passive"))
      (node (ref "U7") (pin "25") (pinfunction "P3[5]_25") (pintype "bidirectional"))
    )
    (net (code "48") (name "THERM-REF-HIGH") (class "Default")
      (node (ref "R1") (pin "2") (pinfunction "2_2") (pintype "passive"))
      (node (ref "U7") (pin "26") (pinfunction "P3[6]_26") (pintype "bidirectional"))
      (node (ref "U7") (pin "3") (pinfunction "P1[3]_3") (pintype "bidirectional"))
    )
    (net (code "49") (name "TIA_IN") (class "Default")
      (node (ref "C10") (pin "1") (pinfunction "1_1") (pintype "passive"))
      (node (ref "D1") (pin "CATHODE") (pinfunction "C1_CATHODE") (pintype "passive"))
      (node (ref "R12") (pin "1") (pinfunction "1_1") (pintype "passive"))
      (node (ref "U7") (pin "11") (pinfunction "P2[1]_11") (pintype "bidirectional"))
    )
    (net (code "50") (name "TIA_OUT") (class "Default")
      (node (ref "C10") (pin "2") (pinfunction "2_2") (pintype "passive"))
      (node (ref "R12") (pin "2") (pinfunction "2_2") (pintype "passive"))
      (node (ref "R17") (pin "2") (pinfunction "2_2") (pintype "passive"))
      (node (ref "U7") (pin "12") (pinfunction "P2[2]_12") (pintype "bidirectional"))
    )
    (net (code "51") (name "UARTRX") (class "Default")
      (node (ref "U$1") (pin "TX") (pinfunction "TX_TX") (pintype "bidirectional"))
      (node (ref "U7") (pin "48") (pinfunction "P1[0]_48") (pintype "bidirectional"))
    )
    (net (code "52") (name "UARTTX") (class "Default")
      (node (ref "U$1") (pin "RX") (pinfunction "RX_RX") (pintype "bidirectional"))
      (node (ref "U7") (pin "1") (pinfunction "P1[1]_1") (pintype "bidirectional"))
    )
    (net (code "53") (name "V33") (class "Default")
      (node (ref "J5") (pin "3") (pinfunction "3_3") (pintype "passive"))
      (node (ref "R32") (pin "1") (pinfunction "1_1") (pintype "passive"))
      (node (ref "U$1") (pin "3.3V") (pinfunction "3.3V_3.3V") (pintype "bidirectional"))
    )
    (net (code "54") (name "V50") (class "Default")
      (node (ref "J5") (pin "1") (pinfunction "1_1") (pintype "passive"))
      (node (ref "R32") (pin "3") (pinfunction "3_3") (pintype "passive"))
      (node (ref "U$1") (pin "5V") (pinfunction "5V_5V") (pintype "bidirectional"))
    )
    (net (code "55") (name "VCC") (class "Default")
      (node (ref "C1") (pin "2") (pinfunction "2_2") (pintype "passive"))
      (node (ref "C17") (pin "1") (pinfunction "1_1") (pintype "passive"))
      (node (ref "C2") (pin "2") (pinfunction "2_2") (pintype "passive"))
      (node (ref "C3") (pin "2") (pinfunction "2_2") (pintype "passive"))
      (node (ref "C4") (pin "2") (pinfunction "2_2") (pintype "passive"))
      (node (ref "C5") (pin "1") (pinfunction "1_1") (pintype "passive"))
      (node (ref "C6") (pin "1") (pinfunction "1_1") (pintype "passive"))
      (node (ref "C8") (pin "2") (pinfunction "2_2") (pintype "passive"))
      (node (ref "C9") (pin "2") (pinfunction "2_2") (pintype "passive"))
      (node (ref "CLED0") (pin "A") (pinfunction "A_A") (pintype "passive"))
      (node (ref "CLED1") (pin "A") (pinfunction "A_A") (pintype "passive"))
      (node (ref "CLED2") (pin "A") (pinfunction "A_A") (pintype "passive"))
      (node (ref "CLED3") (pin "A") (pinfunction "A_A") (pintype "passive"))
      (node (ref "D1") (pin "ANNODE") (pinfunction "E1_ANNODE") (pintype "passive"))
      (node (ref "J5") (pin "2") (pinfunction "2_2") (pintype "passive"))
      (node (ref "J7") (pin "5") (pinfunction "5_5") (pintype "passive"))
      (node (ref "LED1") (pin "A") (pinfunction "A_A") (pintype "passive"))
      (node (ref "LED2") (pin "A") (pinfunction "A_A") (pintype "passive"))
      (node (ref "PROX") (pin "A") (pinfunction "A_A") (pintype "passive"))
      (node (ref "R10") (pin "1") (pinfunction "1_1") (pintype "passive"))
      (node (ref "R18") (pin "2") (pinfunction "2_2") (pintype "passive"))
      (node (ref "R19") (pin "2") (pinfunction "2_2") (pintype "passive"))
      (node (ref "R2") (pin "3") (pinfunction "3_3") (pintype "passive"))
      (node (ref "R20") (pin "2") (pinfunction "2_2") (pintype "passive"))
      (node (ref "R21") (pin "2") (pinfunction "2_2") (pintype "passive"))
      (node (ref "R22") (pin "1") (pinfunction "1_1") (pintype "passive"))
      (node (ref "R30") (pin "1") (pinfunction "1_1") (pintype "passive"))
      (node (ref "R31") (pin "3") (pinfunction "3_3") (pintype "passive"))
      (node (ref "R32") (pin "2") (pinfunction "2_2") (pintype "passive"))
      (node (ref "R9") (pin "1") (pinfunction "1_1") (pintype "passive"))
      (node (ref "U7") (pin "19") (pinfunction "VDDA2_19") (pintype "bidirectional"))
      (node (ref "U7") (pin "43") (pinfunction "VDDA3_43") (pintype "bidirectional"))
      (node (ref "U7") (pin "47") (pinfunction "VDDD_47") (pintype "bidirectional"))
      (node (ref "U7") (pin "8") (pinfunction "VDDA1_8") (pintype "bidirectional"))
    )
    (net (code "56") (name "VDAC") (class "Default")
      (node (ref "U$1") (pin "A1") (pinfunction "A1_A1") (pintype "bidirectional"))
      (node (ref "U7") (pin "2") (pinfunction "P1[2]_2") (pintype "bidirectional"))
    )
    (net (code "57") (name "VREF") (class "Default")
      (node (ref "C13") (pin "1") (pinfunction "1_1") (pintype "passive"))
      (node (ref "U7") (pin "17") (pinfunction "P2[7]_17") (pintype "bidirectional"))
    )
    (net (code "58") (name "XRES") (class "Default")
      (node (ref "C15") (pin "2") (pinfunction "2_2") (pintype "passive"))
      (node (ref "J7") (pin "3") (pinfunction "3_3") (pintype "passive"))
      (node (ref "R22") (pin "2") (pinfunction "2_2") (pintype "passive"))
      (node (ref "U$1") (pin "RES") (pinfunction "RES_RES") (pintype "bidirectional"))
      (node (ref "U7") (pin "36") (pinfunction "XRES_36") (pintype "bidirectional"))
    )
    (net (code "59") (name "unconnected-(U$1-*D3-PadD3)") (class "Default")
      (node (ref "U$1") (pin "D3") (pinfunction "*D3_D3") (pintype "bidirectional"))
    )
    (net (code "60") (name "unconnected-(U$1-*D6-PadD6)") (class "Default")
      (node (ref "U$1") (pin "D6") (pinfunction "*D6_D6") (pintype "bidirectional"))
    )
    (net (code "61") (name "unconnected-(U$1-*D9-PadD9)") (class "Default")
      (node (ref "U$1") (pin "D9") (pinfunction "*D9_D9") (pintype "bidirectional"))
    )
    (net (code "62") (name "unconnected-(U$1-*D10-PadD10)") (class "Default")
      (node (ref "U$1") (pin "D10") (pinfunction "*D10_D10") (pintype "bidirectional"))
    )
    (net (code "63") (name "unconnected-(U$1-PadA3)") (class "Default")
      (node (ref "U$1") (pin "A3") (pinfunction "A3_A3") (pintype "bidirectional"))
    )
    (net (code "64") (name "unconnected-(U$1-PadA4)") (class "Default")
      (node (ref "U$1") (pin "A4") (pinfunction "A4_A4") (pintype "bidirectional"))
    )
    (net (code "65") (name "unconnected-(U$1-PadA5)") (class "Default")
      (node (ref "U$1") (pin "A5") (pinfunction "A5_A5") (pintype "bidirectional"))
    )
    (net (code "66") (name "unconnected-(U$1-PadAREF)") (class "Default")
      (node (ref "U$1") (pin "AREF") (pinfunction "AREF_AREF") (pintype "bidirectional"))
    )
    (net (code "67") (name "unconnected-(U$1-PadD7)") (class "Default")
      (node (ref "U$1") (pin "D7") (pinfunction "D7_D7") (pintype "bidirectional"))
    )
    (net (code "68") (name "unconnected-(U$1-PadD8)") (class "Default")
      (node (ref "U$1") (pin "D8") (pinfunction "D8_D8") (pintype "bidirectional"))
    )
    (net (code "69") (name "unconnected-(U$1-PadIOREF)") (class "Default")
      (node (ref "U$1") (pin "IOREF") (pinfunction "IOREF_IOREF") (pintype "bidirectional"))
    )
    (net (code "70") (name "unconnected-(U$1-PadVIN)") (class "Default")
      (node (ref "U$1") (pin "VIN") (pinfunction "VIN_VIN") (pintype "bidirectional"))
    )
  )
)
